# stm32f100.net
KiCad netlist of a schematic drawn in EAGLE
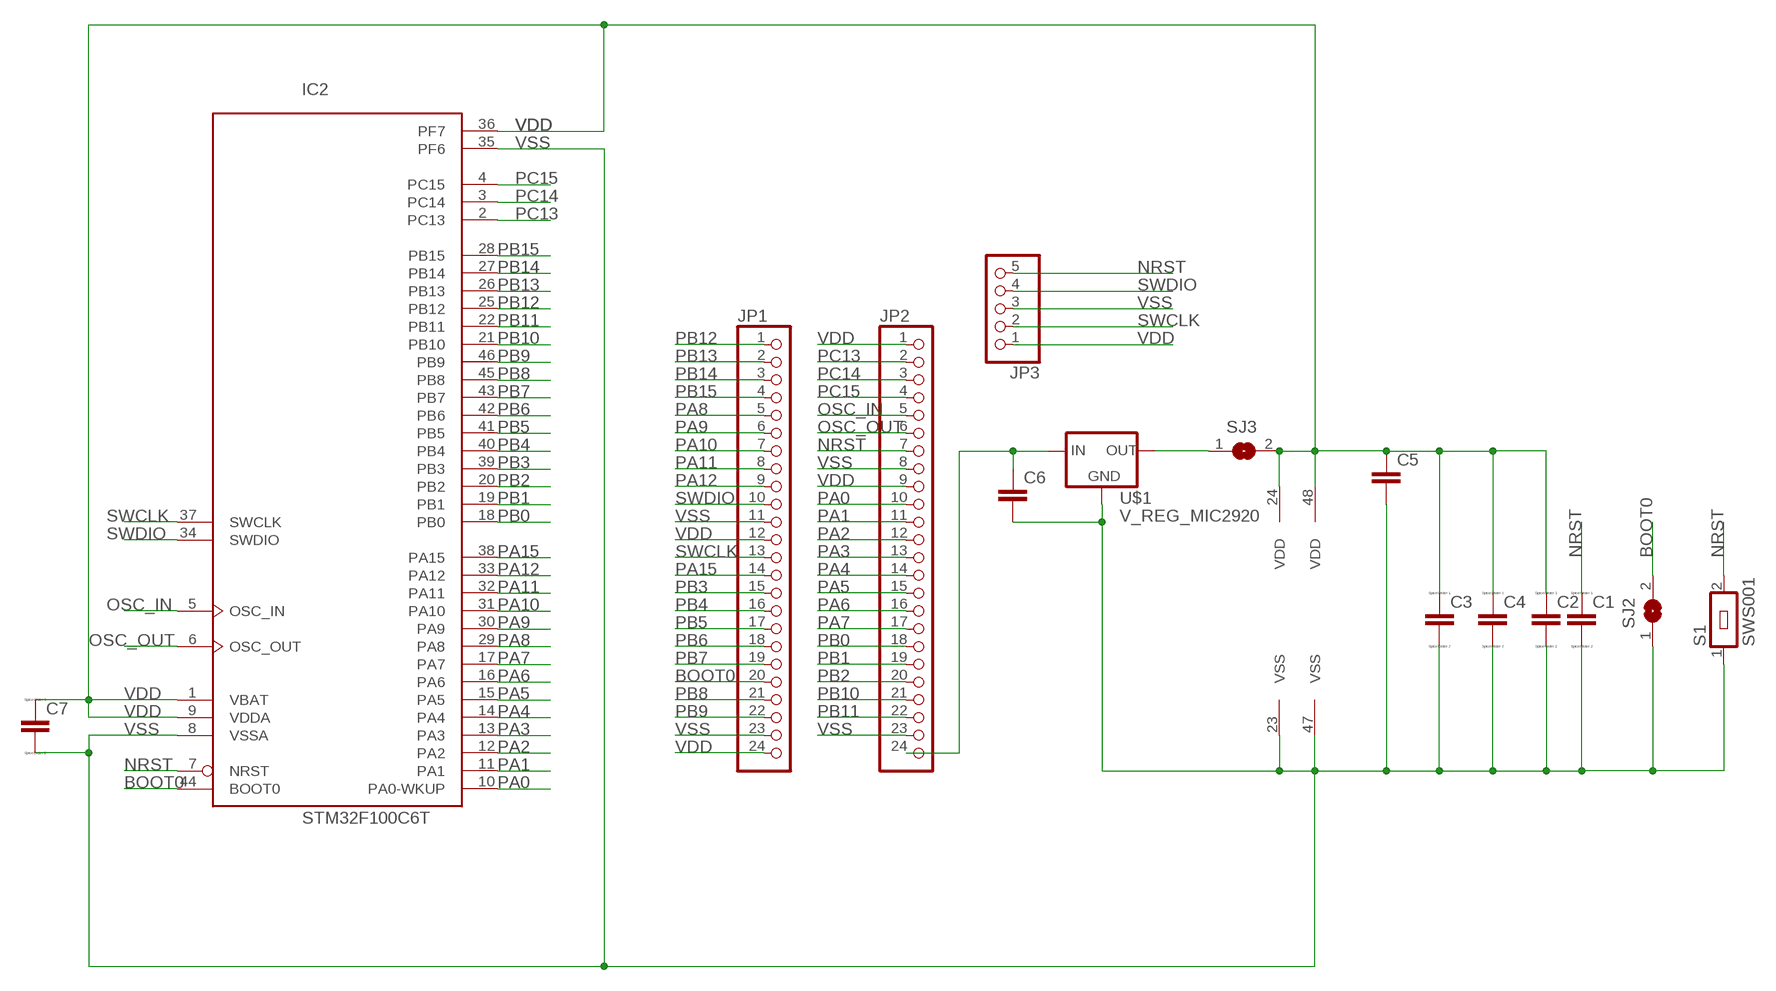
[diagram p0: schematic, sheet 1]

(export (version "E")
  (design (tool "Eeschema 10.0.6"))
  (components
    (comp (ref "C1")
      (value "C-EUC0603K")
      (footprint "eagle-import:C0603K")
      (libsource (lib "eagle-import") (part "resistor_C-EUC0603K"))
    )
    (comp (ref "C2")
      (value "C-EUC0603K")
      (footprint "eagle-import:C0603K")
      (libsource (lib "eagle-import") (part "resistor_C-EUC0603K"))
    )
    (comp (ref "C3")
      (value "C-EUC0603K")
      (footprint "eagle-import:C0603K")
      (libsource (lib "eagle-import") (part "resistor_C-EUC0603K"))
    )
    (comp (ref "C4")
      (value "C-EUC0603K")
      (footprint "eagle-import:C0603K")
      (libsource (lib "eagle-import") (part "resistor_C-EUC0603K"))
    )
    (comp (ref "C5")
      (value "C-EUC1210K")
      (footprint "eagle-import:C1210K")
      (libsource (lib "eagle-import") (part "C-EUC1210K"))
    )
    (comp (ref "C6")
      (value "C-EUC1210K")
      (footprint "eagle-import:C1210K")
      (libsource (lib "eagle-import") (part "C-EUC1210K"))
    )
    (comp (ref "C7")
      (value "C-EUC0603K")
      (footprint "eagle-import:C0603K")
      (libsource (lib "eagle-import") (part "resistor_C-EUC0603K"))
    )
    (comp (ref "IC2")
      (value "STM32F100C6T")
      (footprint "eagle-import:LQFP48")
      (libsource (lib "eagle-import") (part "STM32F100CT6"))
    )
    (comp (ref "JP1")
      (value "PINHD-1X24")
      (footprint "eagle-import:1X24")
      (libsource (lib "eagle-import") (part "PINHD-1X24"))
    )
    (comp (ref "JP2")
      (value "PINHD-1X24")
      (footprint "eagle-import:1X24")
      (libsource (lib "eagle-import") (part "PINHD-1X24"))
    )
    (comp (ref "JP3")
      (value "PINHD-1X5")
      (footprint "eagle-import:1X05")
      (libsource (lib "eagle-import") (part "PINHD-1X5"))
    )
    (comp (ref "S1")
      (value "SWS001")
      (footprint "eagle-import:SMS-001")
      (libsource (lib "eagle-import") (part "SWS001"))
    )
    (comp (ref "SJ2") (value "SJ") (footprint "eagle-import:SJ") (libsource (lib "eagle-import") (part "SJ")))
    (comp (ref "SJ3") (value "SJ") (footprint "eagle-import:SJ") (libsource (lib "eagle-import") (part "SJ")))
    (comp (ref "U$1")
      (value "V_REG_MIC2920")
      (footprint "eagle-import:SOT223")
      (libsource (lib "eagle-import") (part "V_REG_MIC2920"))
    )
  )
  (nets
    (net (code "1") (name "/BOOT0") (class "Default")
      (node (ref "IC2") (pin "44") (pinfunction "BOOT0_44") (pintype "input"))
      (node (ref "JP1") (pin "20") (pinfunction "20_20") (pintype "passive"))
      (node (ref "SJ2") (pin "2") (pinfunction "2_2") (pintype "passive"))
    )
    (net (code "2") (name "/NRST") (class "Default")
      (node (ref "C1") (pin "1") (pinfunction "1_1") (pintype "passive"))
      (node (ref "IC2") (pin "7") (pinfunction "NRST_7") (pintype "bidirectional"))
      (node (ref "JP2") (pin "7") (pinfunction "7_7") (pintype "passive"))
      (node (ref "JP3") (pin "5") (pinfunction "5_5") (pintype "passive"))
      (node (ref "S1") (pin "2") (pinfunction "2_2") (pintype "passive"))
    )
    (net (code "3") (name "/OSC_IN") (class "Default")
      (node (ref "IC2") (pin "5") (pinfunction "OSC_IN_5") (pintype "bidirectional"))
      (node (ref "JP2") (pin "5") (pinfunction "5_5") (pintype "passive"))
    )
    (net (code "4") (name "/OSC_OUT") (class "Default")
      (node (ref "IC2") (pin "6") (pinfunction "OSC_OUT_6") (pintype "bidirectional"))
      (node (ref "JP2") (pin "6") (pinfunction "6_6") (pintype "passive"))
    )
    (net (code "5") (name "/PA0") (class "Default")
      (node (ref "IC2") (pin "10") (pinfunction "PA0-WKUP_10") (pintype "bidirectional"))
      (node (ref "JP2") (pin "10") (pinfunction "10_10") (pintype "passive"))
    )
    (net (code "6") (name "/PA1") (class "Default")
      (node (ref "IC2") (pin "11") (pinfunction "PA1_11") (pintype "bidirectional"))
      (node (ref "JP2") (pin "11") (pinfunction "11_11") (pintype "passive"))
    )
    (net (code "7") (name "/PA2") (class "Default")
      (node (ref "IC2") (pin "12") (pinfunction "PA2_12") (pintype "bidirectional"))
      (node (ref "JP2") (pin "12") (pinfunction "12_12") (pintype "passive"))
    )
    (net (code "8") (name "/PA3") (class "Default")
      (node (ref "IC2") (pin "13") (pinfunction "PA3_13") (pintype "bidirectional"))
      (node (ref "JP2") (pin "13") (pinfunction "13_13") (pintype "passive"))
    )
    (net (code "9") (name "/PA4") (class "Default")
      (node (ref "IC2") (pin "14") (pinfunction "PA4_14") (pintype "bidirectional"))
      (node (ref "JP2") (pin "14") (pinfunction "14_14") (pintype "passive"))
    )
    (net (code "10") (name "/PA5") (class "Default")
      (node (ref "IC2") (pin "15") (pinfunction "PA5_15") (pintype "bidirectional"))
      (node (ref "JP2") (pin "15") (pinfunction "15_15") (pintype "passive"))
    )
    (net (code "11") (name "/PA6") (class "Default")
      (node (ref "IC2") (pin "16") (pinfunction "PA6_16") (pintype "bidirectional"))
      (node (ref "JP2") (pin "16") (pinfunction "16_16") (pintype "passive"))
    )
    (net (code "12") (name "/PA7") (class "Default")
      (node (ref "IC2") (pin "17") (pinfunction "PA7_17") (pintype "bidirectional"))
      (node (ref "JP2") (pin "17") (pinfunction "17_17") (pintype "passive"))
    )
    (net (code "13") (name "/PA8") (class "Default")
      (node (ref "IC2") (pin "29") (pinfunction "PA8_29") (pintype "bidirectional"))
      (node (ref "JP1") (pin "5") (pinfunction "5_5") (pintype "passive"))
    )
    (net (code "14") (name "/PA9") (class "Default")
      (node (ref "IC2") (pin "30") (pinfunction "PA9_30") (pintype "bidirectional"))
      (node (ref "JP1") (pin "6") (pinfunction "6_6") (pintype "passive"))
    )
    (net (code "15") (name "/PA10") (class "Default")
      (node (ref "IC2") (pin "31") (pinfunction "PA10_31") (pintype "bidirectional"))
      (node (ref "JP1") (pin "7") (pinfunction "7_7") (pintype "passive"))
    )
    (net (code "16") (name "/PA11") (class "Default")
      (node (ref "IC2") (pin "32") (pinfunction "PA11_32") (pintype "bidirectional"))
      (node (ref "JP1") (pin "8") (pinfunction "8_8") (pintype "passive"))
    )
    (net (code "17") (name "/PA12") (class "Default")
      (node (ref "IC2") (pin "33") (pinfunction "PA12_33") (pintype "bidirectional"))
      (node (ref "JP1") (pin "9") (pinfunction "9_9") (pintype "passive"))
    )
    (net (code "18") (name "/PA15") (class "Default")
      (node (ref "IC2") (pin "38") (pinfunction "PA15_38") (pintype "bidirectional"))
      (node (ref "JP1") (pin "14") (pinfunction "14_14") (pintype "passive"))
    )
    (net (code "19") (name "/PB0") (class "Default")
      (node (ref "IC2") (pin "18") (pinfunction "PB0_18") (pintype "bidirectional"))
      (node (ref "JP2") (pin "18") (pinfunction "18_18") (pintype "passive"))
    )
    (net (code "20") (name "/PB1") (class "Default")
      (node (ref "IC2") (pin "19") (pinfunction "PB1_19") (pintype "bidirectional"))
      (node (ref "JP2") (pin "19") (pinfunction "19_19") (pintype "passive"))
    )
    (net (code "21") (name "/PB2") (class "Default")
      (node (ref "IC2") (pin "20") (pinfunction "PB2_20") (pintype "bidirectional"))
      (node (ref "JP2") (pin "20") (pinfunction "20_20") (pintype "passive"))
    )
    (net (code "22") (name "/PB3") (class "Default")
      (node (ref "IC2") (pin "39") (pinfunction "PB3_39") (pintype "bidirectional"))
      (node (ref "JP1") (pin "15") (pinfunction "15_15") (pintype "passive"))
    )
    (net (code "23") (name "/PB4") (class "Default")
      (node (ref "IC2") (pin "40") (pinfunction "PB4_40") (pintype "bidirectional"))
      (node (ref "JP1") (pin "16") (pinfunction "16_16") (pintype "passive"))
    )
    (net (code "24") (name "/PB5") (class "Default")
      (node (ref "IC2") (pin "41") (pinfunction "PB5_41") (pintype "bidirectional"))
      (node (ref "JP1") (pin "17") (pinfunction "17_17") (pintype "passive"))
    )
    (net (code "25") (name "/PB6") (class "Default")
      (node (ref "IC2") (pin "42") (pinfunction "PB6_42") (pintype "bidirectional"))
      (node (ref "JP1") (pin "18") (pinfunction "18_18") (pintype "passive"))
    )
    (net (code "26") (name "/PB7") (class "Default")
      (node (ref "IC2") (pin "43") (pinfunction "PB7_43") (pintype "bidirectional"))
      (node (ref "JP1") (pin "19") (pinfunction "19_19") (pintype "passive"))
    )
    (net (code "27") (name "/PB8") (class "Default")
      (node (ref "IC2") (pin "45") (pinfunction "PB8_45") (pintype "bidirectional"))
      (node (ref "JP1") (pin "21") (pinfunction "21_21") (pintype "passive"))
    )
    (net (code "28") (name "/PB9") (class "Default")
      (node (ref "IC2") (pin "46") (pinfunction "PB9_46") (pintype "bidirectional"))
      (node (ref "JP1") (pin "22") (pinfunction "22_22") (pintype "passive"))
    )
    (net (code "29") (name "/PB10") (class "Default")
      (node (ref "IC2") (pin "21") (pinfunction "PB10_21") (pintype "bidirectional"))
      (node (ref "JP2") (pin "21") (pinfunction "21_21") (pintype "passive"))
    )
    (net (code "30") (name "/PB11") (class "Default")
      (node (ref "IC2") (pin "22") (pinfunction "PB11_22") (pintype "bidirectional"))
      (node (ref "JP2") (pin "22") (pinfunction "22_22") (pintype "passive"))
    )
    (net (code "31") (name "/PB12") (class "Default")
      (node (ref "IC2") (pin "25") (pinfunction "PB12_25") (pintype "bidirectional"))
      (node (ref "JP1") (pin "1") (pinfunction "1_1") (pintype "passive"))
    )
    (net (code "32") (name "/PB13") (class "Default")
      (node (ref "IC2") (pin "26") (pinfunction "PB13_26") (pintype "bidirectional"))
      (node (ref "JP1") (pin "2") (pinfunction "2_2") (pintype "passive"))
    )
    (net (code "33") (name "/PB14") (class "Default")
      (node (ref "IC2") (pin "27") (pinfunction "PB14_27") (pintype "bidirectional"))
      (node (ref "JP1") (pin "3") (pinfunction "3_3") (pintype "passive"))
    )
    (net (code "34") (name "/PB15") (class "Default")
      (node (ref "IC2") (pin "28") (pinfunction "PB15_28") (pintype "bidirectional"))
      (node (ref "JP1") (pin "4") (pinfunction "4_4") (pintype "passive"))
    )
    (net (code "35") (name "/PC13") (class "Default")
      (node (ref "IC2") (pin "2") (pinfunction "PC13_2") (pintype "bidirectional"))
      (node (ref "JP2") (pin "2") (pinfunction "2_2") (pintype "passive"))
    )
    (net (code "36") (name "/PC14") (class "Default")
      (node (ref "IC2") (pin "3") (pinfunction "PC14_3") (pintype "bidirectional"))
      (node (ref "JP2") (pin "3") (pinfunction "3_3") (pintype "passive"))
    )
    (net (code "37") (name "/PC15") (class "Default")
      (node (ref "IC2") (pin "4") (pinfunction "PC15_4") (pintype "bidirectional"))
      (node (ref "JP2") (pin "4") (pinfunction "4_4") (pintype "passive"))
    )
    (net (code "38") (name "/SWCLK") (class "Default")
      (node (ref "IC2") (pin "37") (pinfunction "SWCLK_37") (pintype "bidirectional"))
      (node (ref "JP1") (pin "13") (pinfunction "13_13") (pintype "passive"))
      (node (ref "JP3") (pin "2") (pinfunction "2_2") (pintype "passive"))
    )
    (net (code "39") (name "/SWDIO") (class "Default")
      (node (ref "IC2") (pin "34") (pinfunction "SWDIO_34") (pintype "bidirectional"))
      (node (ref "JP1") (pin "10") (pinfunction "10_10") (pintype "passive"))
      (node (ref "JP3") (pin "4") (pinfunction "4_4") (pintype "passive"))
    )
    (net (code "40") (name "/VDD") (class "Default")
      (node (ref "C2") (pin "1") (pinfunction "1_1") (pintype "passive"))
      (node (ref "C3") (pin "1") (pinfunction "1_1") (pintype "passive"))
      (node (ref "C4") (pin "1") (pinfunction "1_1") (pintype "passive"))
      (node (ref "C5") (pin "1") (pinfunction "1_1") (pintype "passive"))
      (node (ref "C7") (pin "1") (pinfunction "1_1") (pintype "passive"))
      (node (ref "IC2") (pin "1") (pinfunction "VBAT_1") (pintype "power_in"))
      (node (ref "IC2") (pin "24") (pinfunction "VDD_24") (pintype "power_in"))
      (node (ref "IC2") (pin "36") (pinfunction "PF7_36") (pintype "bidirectional"))
      (node (ref "IC2") (pin "48") (pinfunction "VDD_48") (pintype "power_in"))
      (node (ref "IC2") (pin "9") (pinfunction "VDDA_9") (pintype "power_in"))
      (node (ref "JP1") (pin "12") (pinfunction "12_12") (pintype "passive"))
      (node (ref "JP1") (pin "24") (pinfunction "24_24") (pintype "passive"))
      (node (ref "JP2") (pin "1") (pinfunction "1_1") (pintype "passive"))
      (node (ref "JP2") (pin "9") (pinfunction "9_9") (pintype "passive"))
      (node (ref "JP3") (pin "1") (pinfunction "1_1") (pintype "passive"))
      (node (ref "SJ3") (pin "2") (pinfunction "2_2") (pintype "passive"))
    )
    (net (code "41") (name "/VSS") (class "Default")
      (node (ref "C1") (pin "2") (pinfunction "2_2") (pintype "passive"))
      (node (ref "C2") (pin "2") (pinfunction "2_2") (pintype "passive"))
      (node (ref "C3") (pin "2") (pinfunction "2_2") (pintype "passive"))
      (node (ref "C4") (pin "2") (pinfunction "2_2") (pintype "passive"))
      (node (ref "C5") (pin "2") (pinfunction "2_2") (pintype "passive"))
      (node (ref "C6") (pin "2") (pinfunction "2_2") (pintype "passive"))
      (node (ref "C7") (pin "2") (pinfunction "2_2") (pintype "passive"))
      (node (ref "IC2") (pin "23") (pinfunction "VSS_23") (pintype "power_in"))
      (node (ref "IC2") (pin "35") (pinfunction "PF6_35") (pintype "bidirectional"))
      (node (ref "IC2") (pin "47") (pinfunction "VSS_47") (pintype "power_in"))
      (node (ref "IC2") (pin "8") (pinfunction "VSSA_8") (pintype "power_in"))
      (node (ref "JP1") (pin "11") (pinfunction "11_11") (pintype "passive"))
      (node (ref "JP1") (pin "23") (pinfunction "23_23") (pintype "passive"))
      (node (ref "JP2") (pin "23") (pinfunction "23_23") (pintype "passive"))
      (node (ref "JP2") (pin "8") (pinfunction "8_8") (pintype "passive"))
      (node (ref "JP3") (pin "3") (pinfunction "3_3") (pintype "passive"))
      (node (ref "S1") (pin "1") (pinfunction "1_1") (pintype "passive"))
      (node (ref "SJ2") (pin "1") (pinfunction "1_1") (pintype "passive"))
      (node (ref "U$1") (pin "1") (pinfunction "GND_1") (pintype "input"))
    )
    (net (code "42") (name "Net-(SJ3-Pad1)") (class "Default")
      (node (ref "SJ3") (pin "1") (pinfunction "1_1") (pintype "passive"))
      (node (ref "U$1") (pin "2") (pinfunction "OUT_2") (pintype "power_in"))
      (node (ref "U$1") (pin "4") (pinfunction "OUT_4") (pintype "power_in"))
    )
    (net (code "43") (name "Net-(U$1-IN)") (class "Default")
      (node (ref "C6") (pin "1") (pinfunction "1_1") (pintype "passive"))
      (node (ref "JP2") (pin "24") (pinfunction "24_24") (pintype "passive"))
      (node (ref "U$1") (pin "3") (pinfunction "IN_3") (pintype "input"))
    )
  )
)
